# Boost_Convertor_V1_Schematic.net
KiCad netlist of a schematic drawn in Altium Designer
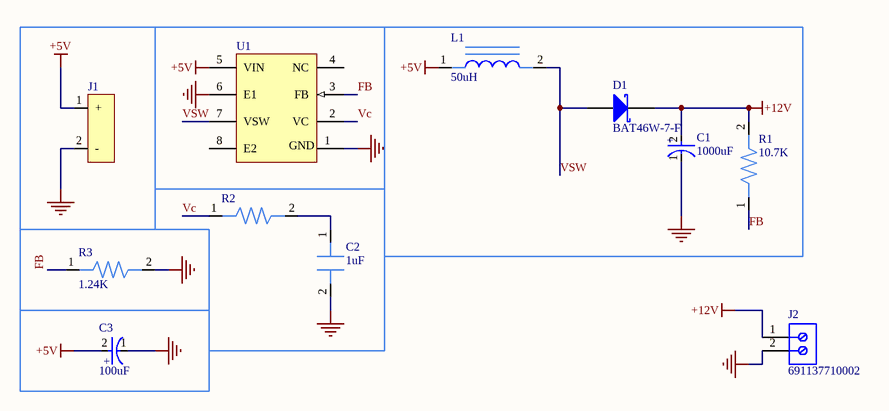
[diagram p0: Boost Convertor V1 Schematic.SchDoc]

(export (version "E")
  (design (tool "Eeschema 10.0.6"))
  (components
    (comp (ref "C1")
      (value "1000uF")
      (footprint "25PX1000MEFCT810X16")
      (fields
        (field (name "MANUFACTURER") "Rubycon")
        (field (name "MANUFACTURER PART NUMBER") "16ZLH1000MEFC10X16")
      )
      (libsource (lib "Boost") (part "16ZLH1000MEFC10X16"))
    )
    (comp (ref "C2")
      (value "1uF")
      (footprint "C1210C105K5RACTU")
      (description "Ceramic Capacitor 1uF")
      (fields
        (field (name "MANUFACTURER") "KEMET")
        (field (name "MANUFACTURER PART NUMBER") "ESL105M100AC3AA")
      )
      (libsource (lib "Boost") (part "CL10B105KA8NNNC"))
    )
    (comp (ref "C3")
      (value "100uF")
      (footprint "35ZLH100MEFC6.3X11")
      (description "CAP ALUM 100UF 20% 35V RADIAL")
      (fields (field (name "VOLTAGE") "35V") (field (name "TOLERANCE") "20%"))
      (libsource (lib "Boost") (part "a00bbbee19879c290e62620ae7e47b1"))
    )
    (comp (ref "D1")
      (value "BAT46W-7-F")
      (footprint "DIOD-SOD-123-2_V")
      (description "Surface Mount Schottky Barrier Diode, 100 V, -55 to 125 degC, 2-Pin SOD123, RoHS, Tape and Reel")
      (fields (field (name "MANUFACTURER") "Diodes Inc"))
      (libsource (lib "Altium Content Vault") (part "DIOD-DSKY-A1K2-2"))
    )
    (comp (ref "J1") (value "0022013037") (libsource (lib "Boost") (part "Molex Connector")))
    (comp (ref "J2")
      (value "691137710002")
      (footprint "691137710002")
      (libsource (lib "Altium Content Vault") (part "TBL - 1R - 02P - Screw"))
    )
    (comp (ref "L1")
      (value "50uH")
      (footprint "CTX50-1-52-R")
      (description "General Purpose Inductor, 50uH, 1 Element, Iron-Core")
      (fields
        (field (name "MANUFACTURER") "Eaton Cooper")
        (field (name "MANUFACTURER PART NUMBER") "CTX50-1-52-R")
      )
      (libsource (lib "Boost") (part "CTX50-1-52-R"))
    )
    (comp (ref "R1")
      (value "10.7K")
      (footprint "RC0805FR-0710K7L")
      (description "Fixed Resistor, Metal Film, 0.25W, 10700ohm, 250V, 1% +/-Tol, -100,100ppm/Cel")
      (fields
        (field (name "MANUFACTURER") "Yageo")
        (field (name "MANUFACTURER PART NUMBER") "MFR-25FBF52-10K7")
      )
      (libsource (lib "Boost") (part "RC0805FR-0710K7L"))
    )
    (comp (ref "R2")
      (value "~")
      (footprint "RC0805FR-071KL")
      (description "Fixed Resistor, Carbon Film, 0.25W, 1000ohm, 350V, 5% +/-Tol, -400,0ppm/Cel, Through Hole Mount")
      (fields
        (field (name "MANUFACTURER") "Stackpole Electronics")
        (field (name "MANUFACTURER PART NUMBER") "CF14JT1K00")
      )
      (libsource (lib "Boost") (part "RC0805FR-071KL"))
    )
    (comp (ref "R3")
      (value "1.24K")
      (footprint "RC0805FR-071K24L")
      (description "Fixed Resistor, Metal Film, 0.25W, 1240ohm, 250V, 1% +/-Tol, -100,100ppm/Cel")
      (fields
        (field (name "MANUFACTURER") "Yageo")
        (field (name "MANUFACTURER PART NUMBER") "MFR-25FBF52-1K24")
      )
      (libsource (lib "Boost") (part "RC0805FR-071K24L"))
    )
    (comp (ref "U1")
      (value "LT1172CN8#PBF")
      (footprint "LT1172CN8#PBF-ND")
      (description "100 kHz, 1.25 A, High Efficiency Switching Regulator, 8-pin DIP (N8-8), 0 to 100 degC, Pb-Free")
      (fields (field (name "MANUFACTURER") "Linear Technology"))
      (libsource (lib "Boost") (part "LT-LT1172-X8-8"))
    )
  )
  (nets
    (net (code "1") (name "+5V") (class "Default")
      (node (ref "C3") (pin "2") (pinfunction "A_2") (pintype "passive"))
      (node (ref "J1") (pin "1") (pinfunction "+_1") (pintype "passive"))
      (node (ref "L1") (pin "1") (pinfunction "1_1") (pintype "passive"))
      (node (ref "U1") (pin "5") (pinfunction "VIN_5") (pintype "power_in"))
    )
    (net (code "2") (name "+12V") (class "Default")
      (node (ref "C1") (pin "2") (pinfunction "A_2") (pintype "passive"))
      (node (ref "D1") (pin "2") (pinfunction "K_2") (pintype "passive"))
      (node (ref "J2") (pin "1") (pinfunction "1_1") (pintype "passive"))
      (node (ref "R1") (pin "2") (pinfunction "2_2") (pintype "passive"))
    )
    (net (code "3") (name "/FB") (class "Default")
      (node (ref "R1") (pin "1") (pinfunction "1_1") (pintype "passive"))
      (node (ref "R3") (pin "1") (pinfunction "1_1") (pintype "passive"))
      (node (ref "U1") (pin "3") (pinfunction "FB_3") (pintype "input"))
    )
    (net (code "4") (name "/VSW") (class "Default")
      (node (ref "D1") (pin "1") (pinfunction "A_1") (pintype "passive"))
      (node (ref "L1") (pin "2") (pinfunction "2_2") (pintype "passive"))
      (node (ref "U1") (pin "7") (pinfunction "VSW_7") (pintype "power_in"))
    )
    (net (code "5") (name "/Vc") (class "Default")
      (node (ref "R2") (pin "1") (pinfunction "1_1") (pintype "passive"))
      (node (ref "U1") (pin "2") (pinfunction "VC_2") (pintype "passive"))
    )
    (net (code "6") (name "GND") (class "Default")
      (node (ref "C1") (pin "1") (pinfunction "C_1") (pintype "passive"))
      (node (ref "C2") (pin "2") (pinfunction "2_2") (pintype "passive"))
      (node (ref "C3") (pin "1") (pinfunction "C_1") (pintype "passive"))
      (node (ref "J1") (pin "2") (pinfunction "-_2") (pintype "passive"))
      (node (ref "J2") (pin "2") (pinfunction "2_2") (pintype "passive"))
      (node (ref "R3") (pin "2") (pinfunction "2_2") (pintype "passive"))
      (node (ref "U1") (pin "6") (pinfunction "E1_6") (pintype "passive"))
    )
    (net (code "7") (name "Net-(C2-Pad1)") (class "Default")
      (node (ref "C2") (pin "1") (pinfunction "1_1") (pintype "passive"))
      (node (ref "R2") (pin "2") (pinfunction "2_2") (pintype "passive"))
    )
    (net (code "8") (name "unconnected-(U1-E2-Pad8)") (class "Default")
      (node (ref "U1") (pin "8") (pinfunction "E2_8") (pintype "passive"))
    )
    (net (code "9") (name "unconnected-(U1-GND-Pad1)") (class "Default")
      (node (ref "U1") (pin "1") (pinfunction "GND_1") (pintype "power_in"))
    )
    (net (code "10") (name "unconnected-(U1-NC-Pad4)") (class "Default")
      (node (ref "U1") (pin "4") (pinfunction "NC_4") (pintype "passive"))
    )
  )
)
